# PAN_1_0.net
KiCad netlist of a schematic drawn in EAGLE
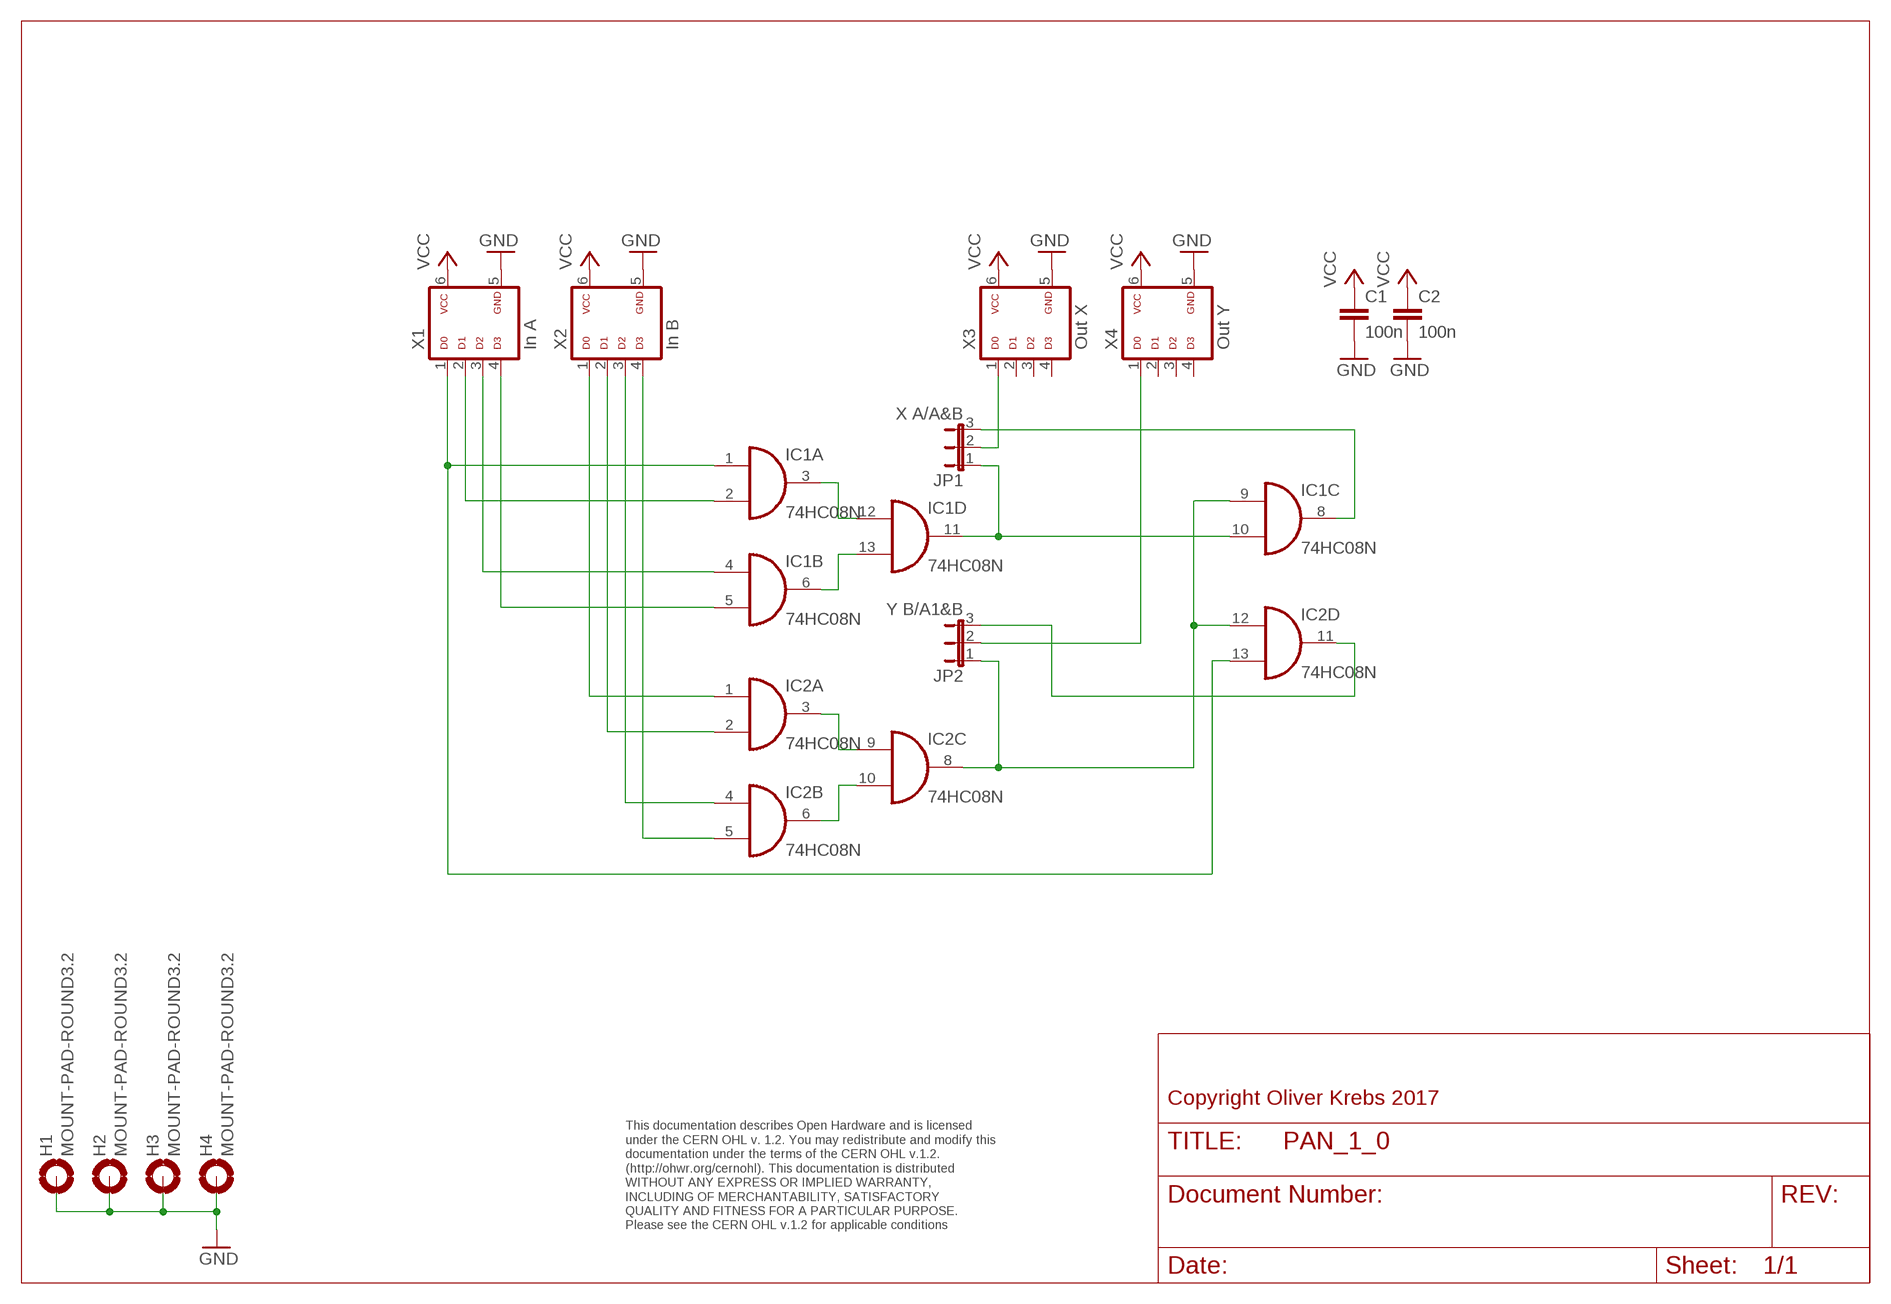
[diagram p0: schematic, sheet 1]

(export (version "E")
  (design (tool "Eeschema 10.0.6"))
  (components
    (comp (ref "C1")
      (value "100n")
      (footprint "eagle-import:C050-025X075")
      (libsource (lib "eagle-import") (part "C-EU050-025X075"))
    )
    (comp (ref "C2")
      (value "100n")
      (footprint "eagle-import:C050-025X075")
      (libsource (lib "eagle-import") (part "C-EU050-025X075"))
    )
    (comp (ref "H1")
      (value "MOUNT-PAD-ROUND3.2")
      (footprint "eagle-import:3,2-PAD")
      (libsource (lib "eagle-import") (part "MOUNT-PAD-ROUND3.2"))
    )
    (comp (ref "H2")
      (value "MOUNT-PAD-ROUND3.2")
      (footprint "eagle-import:3,2-PAD")
      (libsource (lib "eagle-import") (part "MOUNT-PAD-ROUND3.2"))
    )
    (comp (ref "H3")
      (value "MOUNT-PAD-ROUND3.2")
      (footprint "eagle-import:3,2-PAD")
      (libsource (lib "eagle-import") (part "MOUNT-PAD-ROUND3.2"))
    )
    (comp (ref "H4")
      (value "MOUNT-PAD-ROUND3.2")
      (footprint "eagle-import:3,2-PAD")
      (libsource (lib "eagle-import") (part "MOUNT-PAD-ROUND3.2"))
    )
    (comp (ref "IC1")
      (value "74HC08N")
      (footprint "eagle-import:DIL14")
      (libsource (lib "eagle-import") (part "7408NHC"))
    )
    (comp (ref "IC2")
      (value "74HC08N")
      (footprint "eagle-import:DIL14")
      (libsource (lib "eagle-import") (part "7408NHC"))
    )
    (comp (ref "JP1")
      (value "X A/A&B")
      (footprint "eagle-import:JP2-U")
      (libsource (lib "eagle-import") (part "JP2EJP2-U"))
    )
    (comp (ref "JP2")
      (value "Y B/A1&B")
      (footprint "eagle-import:JP2-U")
      (libsource (lib "eagle-import") (part "JP2EJP2-U"))
    )
    (comp (ref "X1")
      (value "In A")
      (footprint "eagle-import:ML-6")
      (libsource (lib "eagle-import") (part "ML6D"))
    )
    (comp (ref "X2")
      (value "In B")
      (footprint "eagle-import:ML-6")
      (libsource (lib "eagle-import") (part "ML6D"))
    )
    (comp (ref "X3")
      (value "Out X")
      (footprint "eagle-import:ML-6")
      (libsource (lib "eagle-import") (part "ML6D"))
    )
    (comp (ref "X4")
      (value "Out Y")
      (footprint "eagle-import:ML-6")
      (libsource (lib "eagle-import") (part "ML6D"))
    )
  )
  (nets
    (net (code "1") (name "GND") (class "Default")
      (node (ref "C1") (pin "2") (pinfunction "2_2") (pintype "passive"))
      (node (ref "C2") (pin "2") (pinfunction "2_2") (pintype "passive"))
      (node (ref "H1") (pin "B3,2") (pinfunction "MOUNT_B3,2") (pintype "passive"))
      (node (ref "H2") (pin "B3,2") (pinfunction "MOUNT_B3,2") (pintype "passive"))
      (node (ref "H3") (pin "B3,2") (pinfunction "MOUNT_B3,2") (pintype "passive"))
      (node (ref "H4") (pin "B3,2") (pinfunction "MOUNT_B3,2") (pintype "passive"))
      (node (ref "X1") (pin "5") (pinfunction "5_5") (pintype "passive"))
      (node (ref "X2") (pin "5") (pinfunction "5_5") (pintype "passive"))
      (node (ref "X3") (pin "5") (pinfunction "5_5") (pintype "passive"))
      (node (ref "X4") (pin "5") (pinfunction "5_5") (pintype "passive"))
    )
    (net (code "2") (name "Net-(IC1A-I0)") (class "Default")
      (node (ref "IC1") (pin "1") (pinfunction "I0_1") (pintype "input"))
      (node (ref "IC2") (pin "13") (pinfunction "I1_13") (pintype "input"))
      (node (ref "X1") (pin "1") (pinfunction "1_1") (pintype "passive"))
    )
    (net (code "3") (name "Net-(IC1A-I1)") (class "Default")
      (node (ref "IC1") (pin "2") (pinfunction "I1_2") (pintype "input"))
      (node (ref "X1") (pin "2") (pinfunction "2_2") (pintype "passive"))
    )
    (net (code "4") (name "Net-(IC1A-O)") (class "Default")
      (node (ref "IC1") (pin "12") (pinfunction "I0_12") (pintype "input"))
      (node (ref "IC1") (pin "3") (pinfunction "O_3") (pintype "output"))
    )
    (net (code "5") (name "Net-(IC1B-I0)") (class "Default")
      (node (ref "IC1") (pin "4") (pinfunction "I0_4") (pintype "input"))
      (node (ref "X1") (pin "3") (pinfunction "3_3") (pintype "passive"))
    )
    (net (code "6") (name "Net-(IC1B-I1)") (class "Default")
      (node (ref "IC1") (pin "5") (pinfunction "I1_5") (pintype "input"))
      (node (ref "X1") (pin "4") (pinfunction "4_4") (pintype "passive"))
    )
    (net (code "7") (name "Net-(IC1B-O)") (class "Default")
      (node (ref "IC1") (pin "13") (pinfunction "I1_13") (pintype "input"))
      (node (ref "IC1") (pin "6") (pinfunction "O_6") (pintype "output"))
    )
    (net (code "8") (name "Net-(IC1C-I0)") (class "Default")
      (node (ref "IC1") (pin "9") (pinfunction "I0_9") (pintype "input"))
      (node (ref "IC2") (pin "12") (pinfunction "I0_12") (pintype "input"))
      (node (ref "IC2") (pin "8") (pinfunction "O_8") (pintype "output"))
      (node (ref "JP2") (pin "1") (pinfunction "1_1") (pintype "passive"))
    )
    (net (code "9") (name "Net-(IC1C-I1)") (class "Default")
      (node (ref "IC1") (pin "10") (pinfunction "I1_10") (pintype "input"))
      (node (ref "IC1") (pin "11") (pinfunction "O_11") (pintype "output"))
      (node (ref "JP1") (pin "1") (pinfunction "1_1") (pintype "passive"))
    )
    (net (code "10") (name "Net-(IC1C-O)") (class "Default")
      (node (ref "IC1") (pin "8") (pinfunction "O_8") (pintype "output"))
      (node (ref "JP1") (pin "3") (pinfunction "3_3") (pintype "passive"))
    )
    (net (code "11") (name "Net-(IC2A-I0)") (class "Default")
      (node (ref "IC2") (pin "1") (pinfunction "I0_1") (pintype "input"))
      (node (ref "X2") (pin "1") (pinfunction "1_1") (pintype "passive"))
    )
    (net (code "12") (name "Net-(IC2A-I1)") (class "Default")
      (node (ref "IC2") (pin "2") (pinfunction "I1_2") (pintype "input"))
      (node (ref "X2") (pin "2") (pinfunction "2_2") (pintype "passive"))
    )
    (net (code "13") (name "Net-(IC2A-O)") (class "Default")
      (node (ref "IC2") (pin "3") (pinfunction "O_3") (pintype "output"))
      (node (ref "IC2") (pin "9") (pinfunction "I0_9") (pintype "input"))
    )
    (net (code "14") (name "Net-(IC2B-I0)") (class "Default")
      (node (ref "IC2") (pin "4") (pinfunction "I0_4") (pintype "input"))
      (node (ref "X2") (pin "3") (pinfunction "3_3") (pintype "passive"))
    )
    (net (code "15") (name "Net-(IC2B-I1)") (class "Default")
      (node (ref "IC2") (pin "5") (pinfunction "I1_5") (pintype "input"))
      (node (ref "X2") (pin "4") (pinfunction "4_4") (pintype "passive"))
    )
    (net (code "16") (name "Net-(IC2B-O)") (class "Default")
      (node (ref "IC2") (pin "10") (pinfunction "I1_10") (pintype "input"))
      (node (ref "IC2") (pin "6") (pinfunction "O_6") (pintype "output"))
    )
    (net (code "17") (name "Net-(IC2D-O)") (class "Default")
      (node (ref "IC2") (pin "11") (pinfunction "O_11") (pintype "output"))
      (node (ref "JP2") (pin "3") (pinfunction "3_3") (pintype "passive"))
    )
    (net (code "18") (name "Net-(JP1-Pad2)") (class "Default")
      (node (ref "JP1") (pin "2") (pinfunction "2_2") (pintype "passive"))
      (node (ref "X3") (pin "1") (pinfunction "1_1") (pintype "passive"))
    )
    (net (code "19") (name "Net-(JP2-Pad2)") (class "Default")
      (node (ref "JP2") (pin "2") (pinfunction "2_2") (pintype "passive"))
      (node (ref "X4") (pin "1") (pinfunction "1_1") (pintype "passive"))
    )
    (net (code "20") (name "VCC") (class "Default")
      (node (ref "C1") (pin "1") (pinfunction "1_1") (pintype "passive"))
      (node (ref "C2") (pin "1") (pinfunction "1_1") (pintype "passive"))
      (node (ref "X1") (pin "6") (pinfunction "6_6") (pintype "passive"))
      (node (ref "X2") (pin "6") (pinfunction "6_6") (pintype "passive"))
      (node (ref "X3") (pin "6") (pinfunction "6_6") (pintype "passive"))
      (node (ref "X4") (pin "6") (pinfunction "6_6") (pintype "passive"))
    )
    (net (code "21") (name "unconnected-(X3-Pad2)") (class "Default")
      (node (ref "X3") (pin "2") (pinfunction "2_2") (pintype "passive"))
    )
    (net (code "22") (name "unconnected-(X3-Pad3)") (class "Default")
      (node (ref "X3") (pin "3") (pinfunction "3_3") (pintype "passive"))
    )
    (net (code "23") (name "unconnected-(X3-Pad4)") (class "Default")
      (node (ref "X3") (pin "4") (pinfunction "4_4") (pintype "passive"))
    )
    (net (code "24") (name "unconnected-(X4-Pad2)") (class "Default")
      (node (ref "X4") (pin "2") (pinfunction "2_2") (pintype "passive"))
    )
    (net (code "25") (name "unconnected-(X4-Pad3)") (class "Default")
      (node (ref "X4") (pin "3") (pinfunction "3_3") (pintype "passive"))
    )
    (net (code "26") (name "unconnected-(X4-Pad4)") (class "Default")
      (node (ref "X4") (pin "4") (pinfunction "4_4") (pintype "passive"))
    )
  )
)
